# zxdos_ps2_usd.net
KiCad netlist of a schematic drawn in EAGLE
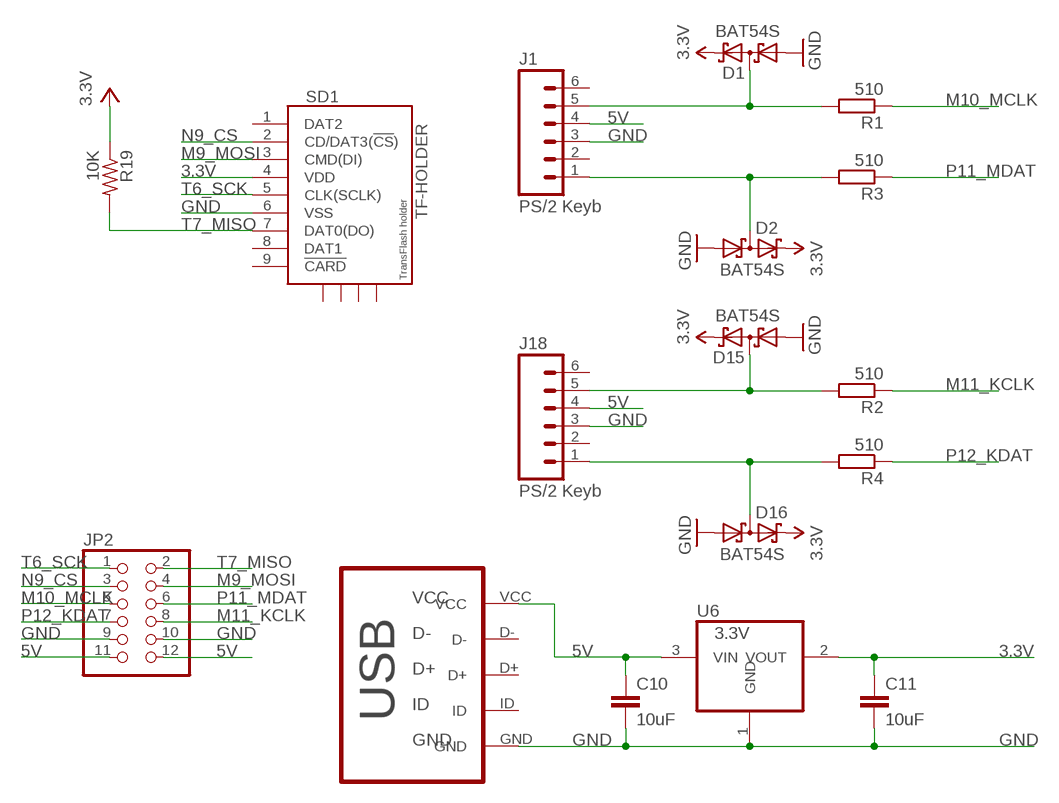
[diagram p0: schematic, sheet 1]

(export (version "E")
  (design (tool "Eeschema 10.0.6"))
  (components
    (comp (ref "C10")
      (value "10uF")
      (footprint "eagle-import:C0805K")
      (libsource (lib "eagle-import") (part "C-EUC0805K"))
    )
    (comp (ref "C11")
      (value "10uF")
      (footprint "eagle-import:C0805K")
      (libsource (lib "eagle-import") (part "C-EUC0805K"))
    )
    (comp (ref "D1")
      (value "BAT54S")
      (footprint "eagle-import:SOT23")
      (libsource (lib "eagle-import") (part "BAT54S"))
    )
    (comp (ref "D2")
      (value "BAT54S")
      (footprint "eagle-import:SOT23")
      (libsource (lib "eagle-import") (part "BAT54S"))
    )
    (comp (ref "D15")
      (value "BAT54S")
      (footprint "eagle-import:SOT23")
      (libsource (lib "eagle-import") (part "BAT54S"))
    )
    (comp (ref "D16")
      (value "BAT54S")
      (footprint "eagle-import:SOT23")
      (libsource (lib "eagle-import") (part "BAT54S"))
    )
    (comp (ref "J1")
      (value "PS/2 Keyb")
      (footprint "eagle-import:DINC_MIN_TM_6_1PRIMARY")
      (libsource (lib "eagle-import") (part "DINC_MIN_TM_6_1"))
    )
    (comp (ref "J17")
      (value "MICRO-USB-B")
      (footprint "eagle-import:MICRO_USB_4_LEGS")
      (libsource (lib "eagle-import") (part "MICRO-USB-B"))
    )
    (comp (ref "J18")
      (value "PS/2 Keyb")
      (footprint "eagle-import:DINC_MIN_TM_6_1PRIMARY")
      (libsource (lib "eagle-import") (part "DINC_MIN_TM_6_1"))
    )
    (comp (ref "JP2")
      (value "PINHD-2X6")
      (footprint "eagle-import:2X06")
      (libsource (lib "eagle-import") (part "PINHD-2X6"))
    )
    (comp (ref "R1")
      (value "510")
      (footprint "eagle-import:R0805")
      (libsource (lib "eagle-import") (part "R-EU_R0805"))
    )
    (comp (ref "R2")
      (value "510")
      (footprint "eagle-import:R0805")
      (libsource (lib "eagle-import") (part "R-EU_R0805"))
    )
    (comp (ref "R3")
      (value "510")
      (footprint "eagle-import:R0805")
      (libsource (lib "eagle-import") (part "R-EU_R0805"))
    )
    (comp (ref "R4")
      (value "510")
      (footprint "eagle-import:R0805")
      (libsource (lib "eagle-import") (part "R-EU_R0805"))
    )
    (comp (ref "R19")
      (value "10K")
      (footprint "eagle-import:R0805")
      (libsource (lib "eagle-import") (part "R-US_R0805"))
    )
    (comp (ref "SD1")
      (value "TF-HOLDER")
      (footprint "eagle-import:TF-PULL")
      (libsource (lib "eagle-import") (part "TF-HOLDER"))
    )
    (comp (ref "U6")
      (value "3.3V")
      (footprint "eagle-import:SOT223")
      (fields (field (name "MPN") "REG1117"))
      (libsource (lib "eagle-import") (part "REG1117"))
    )
  )
  (nets
    (net (code "1") (name "/5V") (class "Default")
      (node (ref "C10") (pin "1") (pinfunction "1_1") (pintype "passive"))
      (node (ref "J1") (pin "4") (pinfunction "4_4") (pintype "passive"))
      (node (ref "J17") (pin "VCC") (pinfunction "VCC_VCC") (pintype "bidirectional"))
      (node (ref "J18") (pin "4") (pinfunction "4_4") (pintype "passive"))
      (node (ref "JP2") (pin "11") (pinfunction "11_11") (pintype "passive"))
      (node (ref "JP2") (pin "12") (pinfunction "12_12") (pintype "passive"))
      (node (ref "U6") (pin "3") (pinfunction "VIN_3") (pintype "input"))
    )
    (net (code "2") (name "/M9_MOSI") (class "Default")
      (node (ref "JP2") (pin "4") (pinfunction "4_4") (pintype "passive"))
      (node (ref "SD1") (pin "3") (pinfunction "CMD(DI)_3") (pintype "bidirectional"))
    )
    (net (code "3") (name "/M10_MCLK") (class "Default")
      (node (ref "JP2") (pin "5") (pinfunction "5_5") (pintype "passive"))
      (node (ref "R1") (pin "1") (pinfunction "1_1") (pintype "passive"))
    )
    (net (code "4") (name "/M11_KCLK") (class "Default")
      (node (ref "JP2") (pin "8") (pinfunction "8_8") (pintype "passive"))
      (node (ref "R2") (pin "1") (pinfunction "1_1") (pintype "passive"))
    )
    (net (code "5") (name "/N9_CS") (class "Default")
      (node (ref "JP2") (pin "3") (pinfunction "3_3") (pintype "passive"))
      (node (ref "SD1") (pin "2") (pinfunction "CD/DAT3(~{CS})_2") (pintype "bidirectional"))
    )
    (net (code "6") (name "/P11_MDAT") (class "Default")
      (node (ref "JP2") (pin "6") (pinfunction "6_6") (pintype "passive"))
      (node (ref "R3") (pin "1") (pinfunction "1_1") (pintype "passive"))
    )
    (net (code "7") (name "/P12_KDAT") (class "Default")
      (node (ref "JP2") (pin "7") (pinfunction "7_7") (pintype "passive"))
      (node (ref "R4") (pin "1") (pinfunction "1_1") (pintype "passive"))
    )
    (net (code "8") (name "/T6_SCK") (class "Default")
      (node (ref "JP2") (pin "1") (pinfunction "1_1") (pintype "passive"))
      (node (ref "SD1") (pin "5") (pinfunction "CLK(SCLK)_5") (pintype "input"))
    )
    (net (code "9") (name "/T7_MISO") (class "Default")
      (node (ref "JP2") (pin "2") (pinfunction "2_2") (pintype "passive"))
      (node (ref "R19") (pin "2") (pinfunction "2_2") (pintype "passive"))
      (node (ref "SD1") (pin "7") (pinfunction "DAT0(DO)_7") (pintype "bidirectional"))
    )
    (net (code "10") (name "3.3V") (class "Default")
      (node (ref "C11") (pin "1") (pinfunction "1_1") (pintype "passive"))
      (node (ref "D1") (pin "2") (pinfunction "C2_2") (pintype "passive"))
      (node (ref "D15") (pin "2") (pinfunction "C2_2") (pintype "passive"))
      (node (ref "D16") (pin "2") (pinfunction "C2_2") (pintype "passive"))
      (node (ref "D2") (pin "2") (pinfunction "C2_2") (pintype "passive"))
      (node (ref "R19") (pin "1") (pinfunction "1_1") (pintype "passive"))
      (node (ref "SD1") (pin "4") (pinfunction "VDD_4") (pintype "power_in"))
      (node (ref "U6") (pin "2") (pinfunction "VOUT_2") (pintype "output"))
    )
    (net (code "11") (name "GND") (class "Default")
      (node (ref "C10") (pin "2") (pinfunction "2_2") (pintype "passive"))
      (node (ref "C11") (pin "2") (pinfunction "2_2") (pintype "passive"))
      (node (ref "D1") (pin "1") (pinfunction "A1_1") (pintype "passive"))
      (node (ref "D15") (pin "1") (pinfunction "A1_1") (pintype "passive"))
      (node (ref "D16") (pin "1") (pinfunction "A1_1") (pintype "passive"))
      (node (ref "D2") (pin "1") (pinfunction "A1_1") (pintype "passive"))
      (node (ref "J1") (pin "3") (pinfunction "3_3") (pintype "passive"))
      (node (ref "J17") (pin "GND") (pinfunction "GND_GND") (pintype "bidirectional"))
      (node (ref "J18") (pin "3") (pinfunction "3_3") (pintype "passive"))
      (node (ref "JP2") (pin "10") (pinfunction "10_10") (pintype "passive"))
      (node (ref "JP2") (pin "9") (pinfunction "9_9") (pintype "passive"))
      (node (ref "SD1") (pin "6") (pinfunction "VSS_6") (pintype "power_in"))
      (node (ref "U6") (pin "1") (pinfunction "GND_1") (pintype "power_in"))
    )
    (net (code "12") (name "Net-(D1-C1A2)") (class "Default")
      (node (ref "D1") (pin "3") (pinfunction "C1A2_3") (pintype "passive"))
      (node (ref "J1") (pin "5") (pinfunction "5_5") (pintype "passive"))
      (node (ref "R1") (pin "2") (pinfunction "2_2") (pintype "passive"))
    )
    (net (code "13") (name "Net-(D2-C1A2)") (class "Default")
      (node (ref "D2") (pin "3") (pinfunction "C1A2_3") (pintype "passive"))
      (node (ref "J1") (pin "1") (pinfunction "1_1") (pintype "passive"))
      (node (ref "R3") (pin "2") (pinfunction "2_2") (pintype "passive"))
    )
    (net (code "14") (name "Net-(D15-C1A2)") (class "Default")
      (node (ref "D15") (pin "3") (pinfunction "C1A2_3") (pintype "passive"))
      (node (ref "J18") (pin "5") (pinfunction "5_5") (pintype "passive"))
      (node (ref "R2") (pin "2") (pinfunction "2_2") (pintype "passive"))
    )
    (net (code "15") (name "Net-(D16-C1A2)") (class "Default")
      (node (ref "D16") (pin "3") (pinfunction "C1A2_3") (pintype "passive"))
      (node (ref "J18") (pin "1") (pinfunction "1_1") (pintype "passive"))
      (node (ref "R4") (pin "2") (pinfunction "2_2") (pintype "passive"))
    )
    (net (code "16") (name "unconnected-(J1-Pad2)") (class "Default")
      (node (ref "J1") (pin "2") (pinfunction "2_2") (pintype "passive"))
    )
    (net (code "17") (name "unconnected-(J1-Pad6)") (class "Default")
      (node (ref "J1") (pin "6") (pinfunction "6_6") (pintype "passive"))
    )
    (net (code "18") (name "unconnected-(J17-PadD+)") (class "Default")
      (node (ref "J17") (pin "D+") (pinfunction "D+_D+") (pintype "bidirectional"))
    )
    (net (code "19") (name "unconnected-(J17-PadD-)") (class "Default")
      (node (ref "J17") (pin "D-") (pinfunction "D-_D-") (pintype "bidirectional"))
    )
    (net (code "20") (name "unconnected-(J17-PadID)") (class "Default")
      (node (ref "J17") (pin "ID") (pinfunction "ID_ID") (pintype "bidirectional"))
    )
    (net (code "21") (name "unconnected-(J18-Pad2)") (class "Default")
      (node (ref "J18") (pin "2") (pinfunction "2_2") (pintype "passive"))
    )
    (net (code "22") (name "unconnected-(J18-Pad6)") (class "Default")
      (node (ref "J18") (pin "6") (pinfunction "6_6") (pintype "passive"))
    )
    (net (code "23") (name "unconnected-(SD1-DAT1-Pad8)") (class "Default")
      (node (ref "SD1") (pin "8") (pinfunction "DAT1_8") (pintype "bidirectional"))
    )
    (net (code "24") (name "unconnected-(SD1-DAT2-Pad1)") (class "Default")
      (node (ref "SD1") (pin "1") (pinfunction "DAT2_1") (pintype "bidirectional"))
    )
    (net (code "25") (name "unconnected-(SD1-PadS1)") (class "Default")
      (node (ref "SD1") (pin "S1") (pinfunction "S1_S1") (pintype "passive"))
    )
    (net (code "26") (name "unconnected-(SD1-PadS2)") (class "Default")
      (node (ref "SD1") (pin "S2") (pinfunction "S2_S2") (pintype "passive"))
    )
    (net (code "27") (name "unconnected-(SD1-PadS3)") (class "Default")
      (node (ref "SD1") (pin "S3") (pinfunction "S3_S3") (pintype "passive"))
    )
    (net (code "28") (name "unconnected-(SD1-PadS4)") (class "Default")
      (node (ref "SD1") (pin "S4") (pinfunction "S4_S4") (pintype "passive"))
    )
    (net (code "29") (name "unconnected-(SD1-~{CARD}-Pad9)") (class "Default")
      (node (ref "SD1") (pin "9") (pinfunction "~{CARD}_9") (pintype "passive"))
    )
  )
)
